# SCH1.net
KiCad netlist of a schematic drawn in Altium Designer
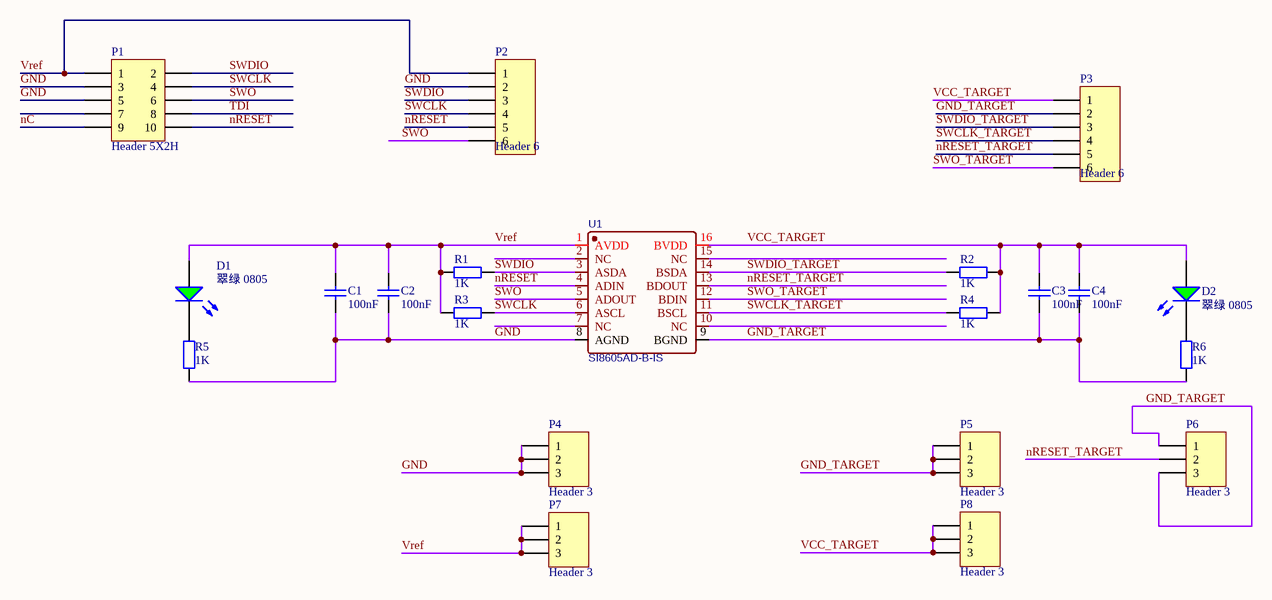
[diagram p0: SCH1.SchDoc]

(export (version "E")
  (design (tool "Eeschema 10.0.6"))
  (components
    (comp (ref "C1")
      (value "100nF")
      (footprint "0603_C")
      (description "0603贴片电容")
      (libsource (lib "Miscellaneous Devices LC") (part "0603 100nF (104) 10% 50V"))
    )
    (comp (ref "C2")
      (value "100nF")
      (footprint "0603_C")
      (description "0603贴片电容")
      (libsource (lib "Miscellaneous Devices LC") (part "0603 100nF (104) 10% 50V"))
    )
    (comp (ref "C3")
      (value "100nF")
      (footprint "0603_C")
      (description "0603贴片电容")
      (libsource (lib "Miscellaneous Devices LC") (part "0603 100nF (104) 10% 50V"))
    )
    (comp (ref "C4")
      (value "100nF")
      (footprint "0603_C")
      (description "0603贴片电容")
      (libsource (lib "Miscellaneous Devices LC") (part "0603 100nF (104) 10% 50V"))
    )
    (comp (ref "D1")
      (value "翠绿 0805")
      (footprint "0805_LED_S1")
      (description "发光二极管")
      (libsource (lib "Miscellaneous Devices LC") (part "0805 翠绿"))
    )
    (comp (ref "D2")
      (value "翠绿 0805")
      (footprint "0805_LED_S1")
      (description "发光二极管")
      (libsource (lib "Miscellaneous Devices LC") (part "0805 翠绿"))
    )
    (comp (ref "P1")
      (value "Header 5X2H")
      (footprint "MHDR2X5")
      (description "Header, 5-Pin, Dual row, Right Angle")
      (fields (field (name "PUBLISHER") "Altium Limited"))
      (libsource (lib "Miscellaneous Connectors") (part "Header 5X2H"))
    )
    (comp (ref "P2")
      (value "Header 6")
      (footprint "HDR1X6")
      (description "Header, 6-Pin")
      (fields (field (name "PUBLISHER") "Altium Limited"))
      (libsource (lib "Miscellaneous Connectors") (part "Header 6"))
    )
    (comp (ref "P3")
      (value "Header 6")
      (footprint "HDR1X6")
      (description "Header, 6-Pin")
      (fields (field (name "PUBLISHER") "Altium Limited"))
      (libsource (lib "Miscellaneous Connectors") (part "Header 6"))
    )
    (comp (ref "P4")
      (value "Header 3")
      (footprint "HDR1X3")
      (description "Header, 3-Pin")
      (fields (field (name "PUBLISHER") "Altium Limited"))
      (libsource (lib "Miscellaneous Connectors") (part "Header 3"))
    )
    (comp (ref "P5")
      (value "Header 3")
      (footprint "HDR1X3")
      (description "Header, 3-Pin")
      (fields (field (name "PUBLISHER") "Altium Limited"))
      (libsource (lib "Miscellaneous Connectors") (part "Header 3"))
    )
    (comp (ref "P6")
      (value "Header 3")
      (footprint "HDR1X3")
      (description "Header, 3-Pin")
      (fields (field (name "PUBLISHER") "Altium Limited"))
      (libsource (lib "Miscellaneous Connectors") (part "Header 3"))
    )
    (comp (ref "P7")
      (value "Header 3")
      (footprint "HDR1X3")
      (description "Header, 3-Pin")
      (fields (field (name "PUBLISHER") "Altium Limited"))
      (libsource (lib "Miscellaneous Connectors") (part "Header 3"))
    )
    (comp (ref "P8")
      (value "Header 3")
      (footprint "HDR1X3")
      (description "Header, 3-Pin")
      (fields (field (name "PUBLISHER") "Altium Limited"))
      (libsource (lib "Miscellaneous Connectors") (part "Header 3"))
    )
    (comp (ref "R1")
      (value "1K")
      (footprint "0603_R")
      (description "0603贴片电阻")
      (fields (field (name "PUBLISHER") "Altium Limited"))
      (libsource (lib "") (part "Res2_2"))
    )
    (comp (ref "R2")
      (value "1K")
      (footprint "0603_R")
      (description "0603贴片电阻")
      (fields (field (name "PUBLISHER") "Altium Limited"))
      (libsource (lib "Miscellaneous Devices") (part "Res2"))
    )
    (comp (ref "R3")
      (value "1K")
      (footprint "0603_R")
      (description "0603贴片电阻")
      (fields (field (name "PUBLISHER") "Altium Limited"))
      (libsource (lib "") (part "Res2_2"))
    )
    (comp (ref "R4")
      (value "1K")
      (footprint "0603_R")
      (description "0603贴片电阻")
      (fields (field (name "PUBLISHER") "Altium Limited"))
      (libsource (lib "Miscellaneous Devices") (part "Res2"))
    )
    (comp (ref "R5")
      (value "1K")
      (footprint "0603_R")
      (description "0603贴片电阻")
      (fields (field (name "PUBLISHER") "Altium Limited"))
      (libsource (lib "") (part "Res2_1"))
    )
    (comp (ref "R6")
      (value "1K")
      (footprint "0603_R")
      (description "0603贴片电阻")
      (fields (field (name "PUBLISHER") "Altium Limited"))
      (libsource (lib "") (part "Res2_2"))
    )
    (comp (ref "U1")
      (value "SI8605AD-B-IS")
      (footprint "si8605")
      (fields (field (name "BOM_SUPPLIER PART") "C430262") (field (name "CONTRIBUTOR") "LCSC"))
      (libsource (lib "Zylib") (part "SI8605AD-B-IS"))
    )
  )
  (nets
    (net (code "1") (name "/GND") (class "Default")
      (node (ref "C1") (pin "1") (pinfunction "1_1") (pintype "passive"))
      (node (ref "C2") (pin "1") (pinfunction "1_1") (pintype "passive"))
      (node (ref "P1") (pin "3") (pinfunction "3_3") (pintype "passive"))
      (node (ref "P1") (pin "5") (pinfunction "5_5") (pintype "passive"))
      (node (ref "P2") (pin "2") (pinfunction "2_2") (pintype "passive"))
      (node (ref "P4") (pin "1") (pinfunction "1_1") (pintype "passive"))
      (node (ref "P4") (pin "2") (pinfunction "2_2") (pintype "passive"))
      (node (ref "P4") (pin "3") (pinfunction "3_3") (pintype "passive"))
      (node (ref "R5") (pin "2") (pinfunction "2_2") (pintype "passive"))
      (node (ref "U1") (pin "8") (pinfunction "AGND_8") (pintype "passive"))
    )
    (net (code "2") (name "/GND_TARGET") (class "Default")
      (node (ref "C3") (pin "1") (pinfunction "1_1") (pintype "passive"))
      (node (ref "C4") (pin "1") (pinfunction "1_1") (pintype "passive"))
      (node (ref "P3") (pin "2") (pinfunction "2_2") (pintype "passive"))
      (node (ref "P5") (pin "1") (pinfunction "1_1") (pintype "passive"))
      (node (ref "P5") (pin "2") (pinfunction "2_2") (pintype "passive"))
      (node (ref "P5") (pin "3") (pinfunction "3_3") (pintype "passive"))
      (node (ref "P6") (pin "1") (pinfunction "1_1") (pintype "passive"))
      (node (ref "P6") (pin "3") (pinfunction "3_3") (pintype "passive"))
      (node (ref "R6") (pin "2") (pinfunction "2_2") (pintype "passive"))
      (node (ref "U1") (pin "9") (pinfunction "BGND_9") (pintype "passive"))
    )
    (net (code "3") (name "/SWCLK") (class "Default")
      (node (ref "P1") (pin "4") (pinfunction "4_4") (pintype "passive"))
      (node (ref "P2") (pin "4") (pinfunction "4_4") (pintype "passive"))
      (node (ref "R3") (pin "1") (pinfunction "1_1") (pintype "passive"))
      (node (ref "U1") (pin "6") (pinfunction "ASCL_6") (pintype "passive"))
    )
    (net (code "4") (name "/SWCLK_TARGET") (class "Default")
      (node (ref "P3") (pin "4") (pinfunction "4_4") (pintype "passive"))
      (node (ref "R4") (pin "1") (pinfunction "1_1") (pintype "passive"))
      (node (ref "U1") (pin "11") (pinfunction "BSCL_11") (pintype "passive"))
    )
    (net (code "5") (name "/SWDIO") (class "Default")
      (node (ref "P1") (pin "2") (pinfunction "2_2") (pintype "passive"))
      (node (ref "P2") (pin "3") (pinfunction "3_3") (pintype "passive"))
      (node (ref "R1") (pin "1") (pinfunction "1_1") (pintype "passive"))
      (node (ref "U1") (pin "3") (pinfunction "ASDA_3") (pintype "passive"))
    )
    (net (code "6") (name "/SWDIO_TARGET") (class "Default")
      (node (ref "P3") (pin "3") (pinfunction "3_3") (pintype "passive"))
      (node (ref "R2") (pin "1") (pinfunction "1_1") (pintype "passive"))
      (node (ref "U1") (pin "14") (pinfunction "BSDA_14") (pintype "passive"))
    )
    (net (code "7") (name "/SWO") (class "Default")
      (node (ref "P1") (pin "6") (pinfunction "6_6") (pintype "passive"))
      (node (ref "P2") (pin "6") (pinfunction "6_6") (pintype "passive"))
      (node (ref "U1") (pin "5") (pinfunction "ADOUT_5") (pintype "passive"))
    )
    (net (code "8") (name "/SWO_TARGET") (class "Default")
      (node (ref "P3") (pin "6") (pinfunction "6_6") (pintype "passive"))
      (node (ref "U1") (pin "12") (pinfunction "BDIN_12") (pintype "passive"))
    )
    (net (code "9") (name "/TDI") (class "Default")
      (node (ref "P1") (pin "8") (pinfunction "8_8") (pintype "passive"))
    )
    (net (code "10") (name "/VCC_TARGET") (class "Default")
      (node (ref "C3") (pin "2") (pinfunction "2_2") (pintype "passive"))
      (node (ref "C4") (pin "2") (pinfunction "2_2") (pintype "passive"))
      (node (ref "D2") (pin "A") (pinfunction "A_A") (pintype "passive"))
      (node (ref "P3") (pin "1") (pinfunction "1_1") (pintype "passive"))
      (node (ref "P8") (pin "1") (pinfunction "1_1") (pintype "passive"))
      (node (ref "P8") (pin "2") (pinfunction "2_2") (pintype "passive"))
      (node (ref "P8") (pin "3") (pinfunction "3_3") (pintype "passive"))
      (node (ref "R2") (pin "2") (pinfunction "2_2") (pintype "passive"))
      (node (ref "R4") (pin "2") (pinfunction "2_2") (pintype "passive"))
      (node (ref "U1") (pin "16") (pinfunction "BVDD_16") (pintype "passive"))
    )
    (net (code "11") (name "/Vref") (class "Default")
      (node (ref "C1") (pin "2") (pinfunction "2_2") (pintype "passive"))
      (node (ref "C2") (pin "2") (pinfunction "2_2") (pintype "passive"))
      (node (ref "D1") (pin "A") (pinfunction "A_A") (pintype "passive"))
      (node (ref "P1") (pin "1") (pinfunction "1_1") (pintype "passive"))
      (node (ref "P2") (pin "1") (pinfunction "1_1") (pintype "passive"))
      (node (ref "P7") (pin "1") (pinfunction "1_1") (pintype "passive"))
      (node (ref "P7") (pin "2") (pinfunction "2_2") (pintype "passive"))
      (node (ref "P7") (pin "3") (pinfunction "3_3") (pintype "passive"))
      (node (ref "R1") (pin "2") (pinfunction "2_2") (pintype "passive"))
      (node (ref "R3") (pin "2") (pinfunction "2_2") (pintype "passive"))
      (node (ref "U1") (pin "1") (pinfunction "AVDD_1") (pintype "passive"))
    )
    (net (code "12") (name "/nC") (class "Default")
      (node (ref "P1") (pin "9") (pinfunction "9_9") (pintype "passive"))
    )
    (net (code "13") (name "/nRESET") (class "Default")
      (node (ref "P1") (pin "10") (pinfunction "10_10") (pintype "passive"))
      (node (ref "P2") (pin "5") (pinfunction "5_5") (pintype "passive"))
      (node (ref "U1") (pin "4") (pinfunction "ADIN_4") (pintype "passive"))
    )
    (net (code "14") (name "/nRESET_TARGET") (class "Default")
      (node (ref "P3") (pin "5") (pinfunction "5_5") (pintype "passive"))
      (node (ref "P6") (pin "2") (pinfunction "2_2") (pintype "passive"))
      (node (ref "U1") (pin "13") (pinfunction "BDOUT_13") (pintype "passive"))
    )
    (net (code "15") (name "Net-(D1-PadK)") (class "Default")
      (node (ref "D1") (pin "K") (pinfunction "K_K") (pintype "passive"))
      (node (ref "R5") (pin "1") (pinfunction "1_1") (pintype "passive"))
    )
    (net (code "16") (name "Net-(D2-PadK)") (class "Default")
      (node (ref "D2") (pin "K") (pinfunction "K_K") (pintype "passive"))
      (node (ref "R6") (pin "1") (pinfunction "1_1") (pintype "passive"))
    )
    (net (code "17") (name "unconnected-(P1-Pad7)") (class "Default")
      (node (ref "P1") (pin "7") (pinfunction "7_7") (pintype "passive"))
    )
    (net (code "18") (name "unconnected-(U1-NC-Pad2)") (class "Default")
      (node (ref "U1") (pin "2") (pinfunction "NC_2") (pintype "passive"))
    )
    (net (code "19") (name "unconnected-(U1-NC-Pad7)") (class "Default")
      (node (ref "U1") (pin "7") (pinfunction "NC_7") (pintype "passive"))
    )
    (net (code "20") (name "unconnected-(U1-NC-Pad10)") (class "Default")
      (node (ref "U1") (pin "10") (pinfunction "NC_10") (pintype "passive"))
    )
    (net (code "21") (name "unconnected-(U1-NC-Pad15)") (class "Default")
      (node (ref "U1") (pin "15") (pinfunction "NC_15") (pintype "passive"))
    )
  )
)
